# Wifi.net
KiCad netlist of a schematic drawn in Altium Designer
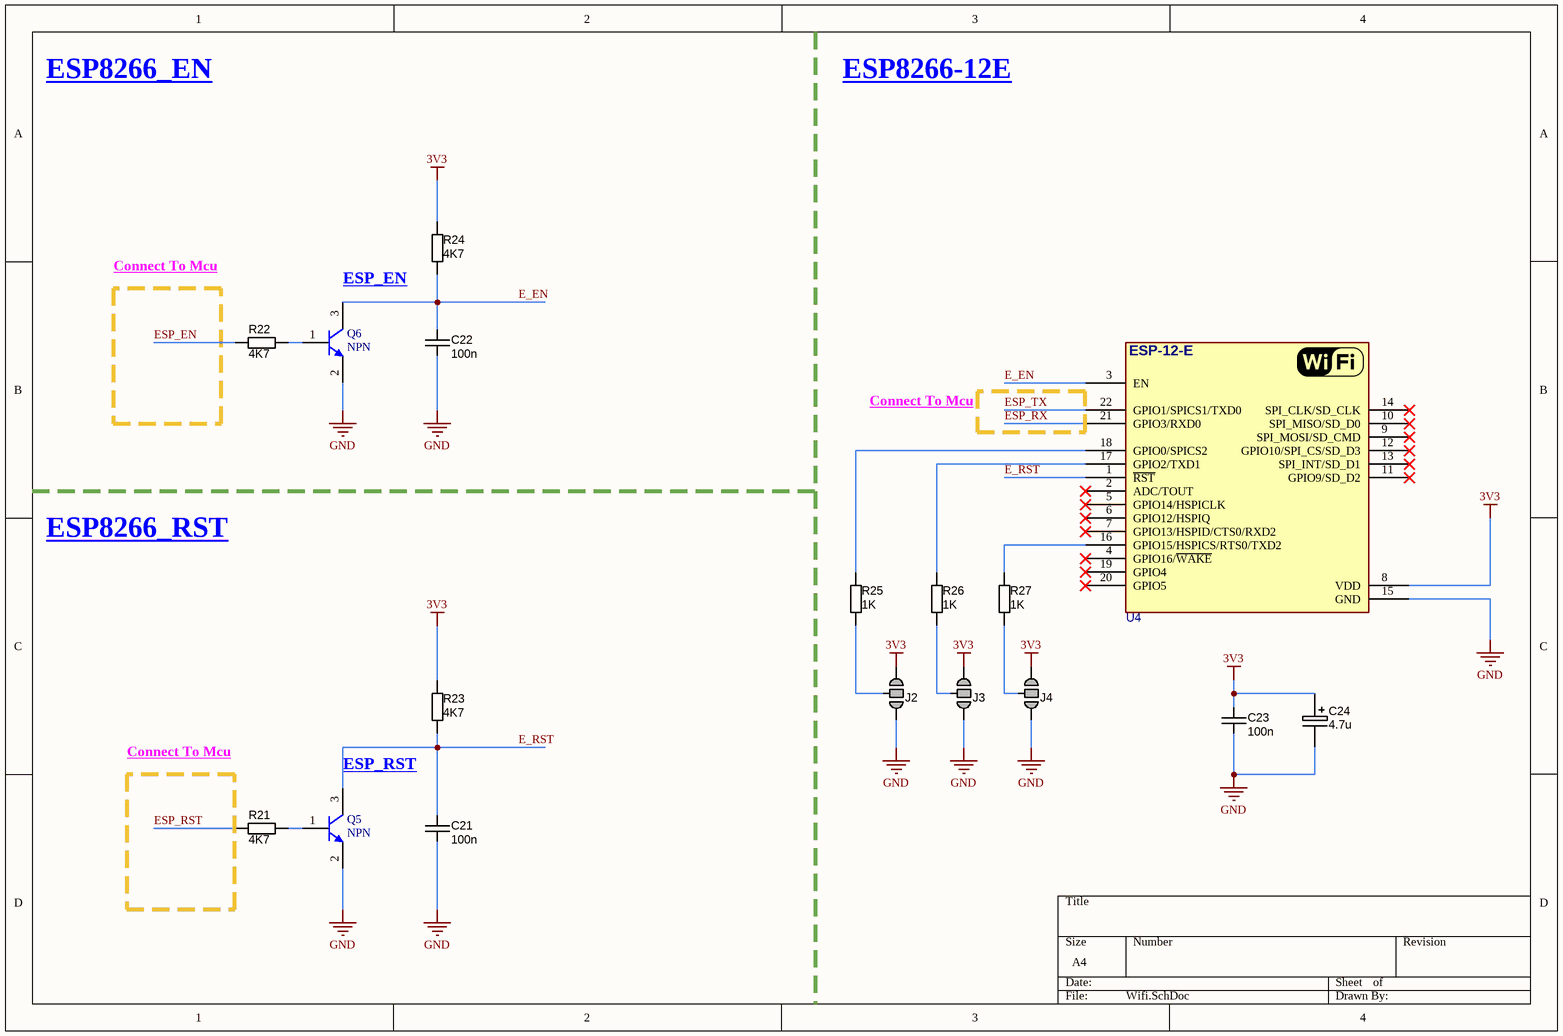
[diagram p0: Wifi.SchDoc]

(export (version "E")
  (design (tool "Eeschema 10.0.6"))
  (components
    (comp (ref "C21")
      (value "100n")
      (footprint "CAPC1608X90N")
      (description "Capacitor SMD Cer 100nF 10% 50V X7R 0603")
      (fields (field (name "TOLERANCE") "±10%") (field (name "Comment") "approved sub OK"))
      (libsource (lib "PBL - Capacitors") (part "CAPC_100n_0603_X7R_50V_10%"))
    )
    (comp (ref "C22")
      (value "100n")
      (footprint "CAPC1608X90N")
      (description "Capacitor SMD Cer 100nF 10% 50V X7R 0603")
      (fields (field (name "TOLERANCE") "±10%") (field (name "Comment") "approved sub OK"))
      (libsource (lib "PBL - Capacitors") (part "CAPC_100n_0603_X7R_50V_10%"))
    )
    (comp (ref "C23")
      (value "100n")
      (footprint "CAPC1608X90N")
      (description "Capacitor SMD Cer 100nF 10% 50V X7R 0603")
      (fields (field (name "TOLERANCE") "±10%") (field (name "Comment") "approved sub OK"))
      (libsource (lib "PBL - Capacitors") (part "CAPC_100n_0603_X7R_50V_10%"))
    )
    (comp (ref "C24")
      (value "4.7u")
      (footprint "C_TN_3528")
      (description "Capacitor SMD Tantalum 10uF 10% 16V 3216-18")
      (fields (field (name "TOLERANCE") "±10%"))
      (libsource (lib "PBL - Capacitors") (part "CAPT_4u7_3216_16V"))
    )
    (comp (ref "J2")
      (value "Jumper")
      (footprint "Jump_3Way")
      (description "SMD jumper")
      (libsource (lib "PBL - Pads and Jumpers") (part "JUMP_3WAY"))
    )
    (comp (ref "J3")
      (value "Jumper")
      (footprint "Jump_3Way")
      (description "SMD jumper")
      (libsource (lib "PBL - Pads and Jumpers") (part "JUMP_3WAY"))
    )
    (comp (ref "J4")
      (value "Jumper")
      (footprint "Jump_3Way")
      (description "SMD jumper")
      (libsource (lib "PBL - Pads and Jumpers") (part "JUMP_3WAY"))
    )
    (comp (ref "Q5")
      (value "NPN")
      (footprint "SOT23-3")
      (description "NPN Bipolar Transistor")
      (fields (field (name "PUBLISHER") "Altium Limited"))
      (libsource (lib "Miscellaneous Devices") (part "NPN"))
    )
    (comp (ref "Q6")
      (value "NPN")
      (footprint "SOT23-3")
      (description "NPN Bipolar Transistor")
      (fields (field (name "PUBLISHER") "Altium Limited"))
      (libsource (lib "Miscellaneous Devices") (part "NPN"))
    )
    (comp (ref "R21")
      (value "4K7")
      (footprint "RESC1608X55N")
      (description "Resistor SMD chip 4.7k Ohm 0.1W 5% 0603")
      (fields (field (name "TOLERANCE") "±5%") (field (name "Comment") "Thick Film"))
      (libsource (lib "PBL - Resistors") (part "RES_4K7_0603_5%"))
    )
    (comp (ref "R22")
      (value "4K7")
      (footprint "RESC1608X55N")
      (description "Resistor SMD chip 4.7k Ohm 0.1W 5% 0603")
      (fields (field (name "TOLERANCE") "±5%") (field (name "Comment") "Thick Film"))
      (libsource (lib "PBL - Resistors") (part "RES_4K7_0603_5%"))
    )
    (comp (ref "R23")
      (value "4K7")
      (footprint "RESC1608X55N")
      (description "Resistor SMD chip 4.7k Ohm 0.1W 5% 0603")
      (fields (field (name "TOLERANCE") "±5%") (field (name "Comment") "Thick Film"))
      (libsource (lib "") (part "RES_4K7_0603_5%_1"))
    )
    (comp (ref "R24")
      (value "4K7")
      (footprint "RESC1608X55N")
      (description "Resistor SMD chip 4.7k Ohm 0.1W 5% 0603")
      (fields (field (name "TOLERANCE") "±5%") (field (name "Comment") "Thick Film"))
      (libsource (lib "") (part "RES_4K7_0603_5%_1"))
    )
    (comp (ref "R25")
      (value "1K")
      (footprint "RESC1608X55N")
      (description "Resistor SMD chip 1k Ohm 0.1W 5% 0603")
      (fields (field (name "TOLERANCE") "±5%") (field (name "Comment") "Thick Film"))
      (libsource (lib "") (part "RES_4K7_0603_5%_1"))
    )
    (comp (ref "R26")
      (value "1K")
      (footprint "RESC1608X55N")
      (description "Resistor SMD chip 1k Ohm 0.1W 5% 0603")
      (fields (field (name "TOLERANCE") "±5%") (field (name "Comment") "Thick Film"))
      (libsource (lib "") (part "RES_4K7_0603_5%_1"))
    )
    (comp (ref "R27")
      (value "1K")
      (footprint "RESC1608X55N")
      (description "Resistor SMD chip 1k Ohm 0.1W 5% 0603")
      (fields (field (name "TOLERANCE") "±5%") (field (name "Comment") "Thick Film"))
      (libsource (lib "") (part "RES_4K7_0603_5%_1"))
    )
    (comp (ref "U4")
      (value "~")
      (footprint "ESP8266_ESP12E")
      (description "ESP8266 ESP-12 Wi-Fi Module")
      (libsource (lib "Module") (part "ESP8266 ESP-12-E"))
    )
  )
  (nets
    (net (code "1") (name "/ESP_EN") (class "Default")
      (node (ref "R22") (pin "1") (pinfunction "1_1") (pintype "passive"))
    )
    (net (code "2") (name "/ESP_RST") (class "Default")
      (node (ref "R21") (pin "1") (pinfunction "1_1") (pintype "passive"))
    )
    (net (code "3") (name "/ESP_RX") (class "Default")
      (node (ref "U4") (pin "21") (pinfunction "GPIO3/RXD0_21") (pintype "passive"))
    )
    (net (code "4") (name "/ESP_TX") (class "Default")
      (node (ref "U4") (pin "22") (pinfunction "GPIO1/SPICS1/TXD0_22") (pintype "passive"))
    )
    (net (code "5") (name "/E_EN") (class "Default")
      (node (ref "C22") (pin "1") (pintype "passive"))
      (node (ref "Q6") (pin "3") (pinfunction "C_3") (pintype "passive"))
      (node (ref "R24") (pin "2") (pinfunction "2_2") (pintype "passive"))
      (node (ref "U4") (pin "3") (pinfunction "EN_3") (pintype "passive"))
    )
    (net (code "6") (name "/E_RST") (class "Default")
      (node (ref "C21") (pin "1") (pintype "passive"))
      (node (ref "Q5") (pin "3") (pinfunction "C_3") (pintype "passive"))
      (node (ref "R23") (pin "2") (pinfunction "2_2") (pintype "passive"))
      (node (ref "U4") (pin "1") (pinfunction "~{RST}_1") (pintype "passive"))
    )
    (net (code "7") (name "3V3") (class "Default")
      (node (ref "C23") (pin "1") (pintype "passive"))
      (node (ref "C24") (pin "1") (pintype "passive"))
      (node (ref "J2") (pin "3") (pinfunction "3_3") (pintype "passive"))
      (node (ref "J3") (pin "3") (pinfunction "3_3") (pintype "passive"))
      (node (ref "J4") (pin "3") (pinfunction "3_3") (pintype "passive"))
      (node (ref "R23") (pin "1") (pinfunction "1_1") (pintype "passive"))
      (node (ref "R24") (pin "1") (pinfunction "1_1") (pintype "passive"))
      (node (ref "U4") (pin "8") (pinfunction "VDD_8") (pintype "passive"))
    )
    (net (code "8") (name "GND") (class "Default")
      (node (ref "C21") (pin "2") (pintype "passive"))
      (node (ref "C22") (pin "2") (pintype "passive"))
      (node (ref "C23") (pin "2") (pintype "passive"))
      (node (ref "C24") (pin "2") (pintype "passive"))
      (node (ref "J2") (pin "1") (pinfunction "1_1") (pintype "passive"))
      (node (ref "J3") (pin "1") (pinfunction "1_1") (pintype "passive"))
      (node (ref "J4") (pin "1") (pinfunction "1_1") (pintype "passive"))
      (node (ref "Q5") (pin "2") (pinfunction "E_2") (pintype "passive"))
      (node (ref "Q6") (pin "2") (pinfunction "E_2") (pintype "passive"))
      (node (ref "U4") (pin "15") (pinfunction "GND_15") (pintype "passive"))
    )
    (net (code "9") (name "Net-(J2-Pad2)") (class "Default")
      (node (ref "J2") (pin "2") (pinfunction "2_2") (pintype "passive"))
      (node (ref "R25") (pin "2") (pinfunction "2_2") (pintype "passive"))
    )
    (net (code "10") (name "Net-(J3-Pad2)") (class "Default")
      (node (ref "J3") (pin "2") (pinfunction "2_2") (pintype "passive"))
      (node (ref "R26") (pin "2") (pinfunction "2_2") (pintype "passive"))
    )
    (net (code "11") (name "Net-(J4-Pad2)") (class "Default")
      (node (ref "J4") (pin "2") (pinfunction "2_2") (pintype "passive"))
      (node (ref "R27") (pin "2") (pinfunction "2_2") (pintype "passive"))
    )
    (net (code "12") (name "Net-(Q5-B)") (class "Default")
      (node (ref "Q5") (pin "1") (pinfunction "B_1") (pintype "passive"))
      (node (ref "R21") (pin "2") (pinfunction "2_2") (pintype "passive"))
    )
    (net (code "13") (name "Net-(Q6-B)") (class "Default")
      (node (ref "Q6") (pin "1") (pinfunction "B_1") (pintype "passive"))
      (node (ref "R22") (pin "2") (pinfunction "2_2") (pintype "passive"))
    )
    (net (code "14") (name "Net-(U4-GPIO0{slash}SPICS2)") (class "Default")
      (node (ref "R25") (pin "1") (pinfunction "1_1") (pintype "passive"))
      (node (ref "U4") (pin "18") (pinfunction "GPIO0/SPICS2_18") (pintype "passive"))
    )
    (net (code "15") (name "Net-(U4-GPIO2{slash}TXD1)") (class "Default")
      (node (ref "R26") (pin "1") (pinfunction "1_1") (pintype "passive"))
      (node (ref "U4") (pin "17") (pinfunction "GPIO2/TXD1_17") (pintype "passive"))
    )
    (net (code "16") (name "Net-(U4-GPIO15{slash}HSPICS{slash}RTS0{slash}TXD2)") (class "Default")
      (node (ref "R27") (pin "1") (pinfunction "1_1") (pintype "passive"))
      (node (ref "U4") (pin "16") (pinfunction "GPIO15/HSPICS/RTS0/TXD2_16") (pintype "passive"))
    )
    (net (code "17") (name "unconnected-(U4-ADC{slash}TOUT-Pad2)") (class "Default")
      (node (ref "U4") (pin "2") (pinfunction "ADC/TOUT_2") (pintype "passive+no_connect"))
    )
    (net (code "18") (name "unconnected-(U4-GPIO4-Pad19)") (class "Default")
      (node (ref "U4") (pin "19") (pinfunction "GPIO4_19") (pintype "passive+no_connect"))
    )
    (net (code "19") (name "unconnected-(U4-GPIO5-Pad20)") (class "Default")
      (node (ref "U4") (pin "20") (pinfunction "GPIO5_20") (pintype "passive+no_connect"))
    )
    (net (code "20") (name "unconnected-(U4-GPIO9{slash}SD_D2-Pad11)") (class "Default")
      (node (ref "U4") (pin "11") (pinfunction "GPIO9/SD_D2_11") (pintype "passive+no_connect"))
    )
    (net (code "21") (name "unconnected-(U4-GPIO10{slash}SPI_CS{slash}SD_D3-Pad12)") (class "Default")
      (node (ref "U4") (pin "12") (pinfunction "GPIO10/SPI_CS/SD_D3_12") (pintype "passive+no_connect"))
    )
    (net (code "22") (name "unconnected-(U4-GPIO12{slash}HSPIQ-Pad6)") (class "Default")
      (node (ref "U4") (pin "6") (pinfunction "GPIO12/HSPIQ_6") (pintype "passive+no_connect"))
    )
    (net (code "23") (name "unconnected-(U4-GPIO13{slash}HSPID{slash}CTS0{slash}RXD2-Pad7)") (class "Default")
      (node (ref "U4") (pin "7") (pinfunction "GPIO13/HSPID/CTS0/RXD2_7") (pintype "passive+no_connect"))
    )
    (net (code "24") (name "unconnected-(U4-GPIO14{slash}HSPICLK-Pad5)") (class "Default")
      (node (ref "U4") (pin "5") (pinfunction "GPIO14/HSPICLK_5") (pintype "passive+no_connect"))
    )
    (net (code "25") (name "unconnected-(U4-GPIO16{slash}~{WAKE}-Pad4)") (class "Default")
      (node (ref "U4") (pin "4") (pinfunction "GPIO16/~{WAKE}_4") (pintype "passive+no_connect"))
    )
    (net (code "26") (name "unconnected-(U4-SPI_CLK{slash}SD_CLK-Pad14)") (class "Default")
      (node (ref "U4") (pin "14") (pinfunction "SPI_CLK/SD_CLK_14") (pintype "passive+no_connect"))
    )
    (net (code "27") (name "unconnected-(U4-SPI_INT{slash}SD_D1-Pad13)") (class "Default")
      (node (ref "U4") (pin "13") (pinfunction "SPI_INT/SD_D1_13") (pintype "passive+no_connect"))
    )
    (net (code "28") (name "unconnected-(U4-SPI_MISO{slash}SD_D0-Pad10)") (class "Default")
      (node (ref "U4") (pin "10") (pinfunction "SPI_MISO/SD_D0_10") (pintype "passive+no_connect"))
    )
    (net (code "29") (name "unconnected-(U4-SPI_MOSI{slash}SD_CMD-Pad9)") (class "Default")
      (node (ref "U4") (pin "9") (pinfunction "SPI_MOSI/SD_CMD_9") (pintype "passive+no_connect"))
    )
  )
)
